# PhaseShifterB.net
KiCad netlist of a schematic drawn in Altium Designer
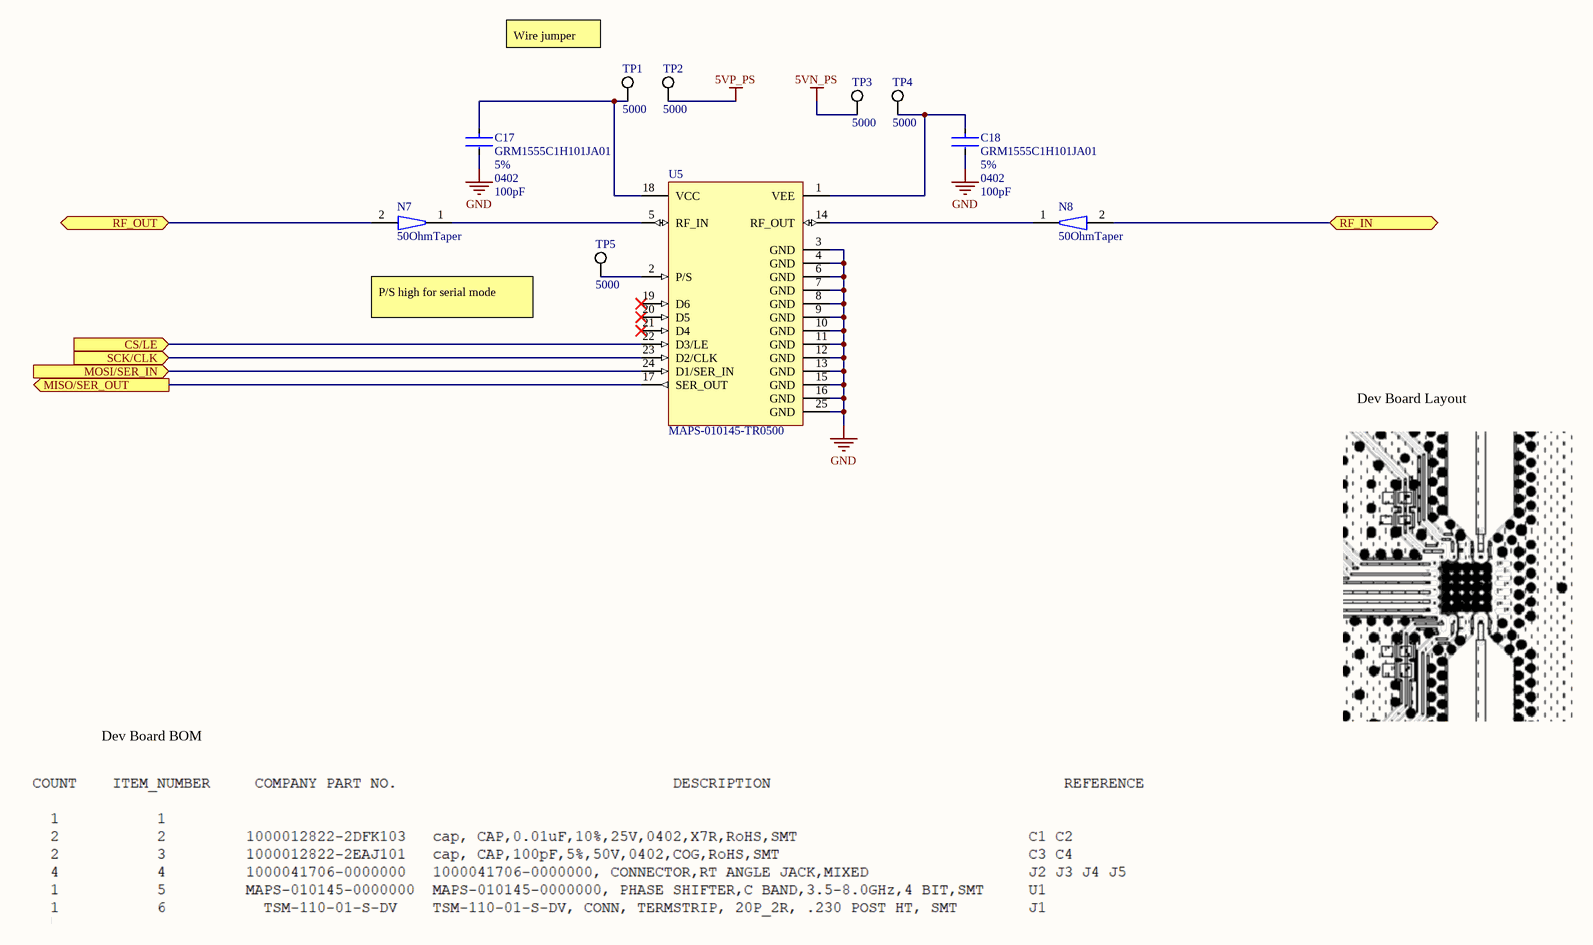
[diagram p0: PhaseShifterB.SchDoc]

(export (version "E")
  (design (tool "Eeschema 10.0.6"))
  (components
    (comp (ref "C17")
      (value "GRM1555C1H101JA01")
      (footprint "Capacitor0402_Murata")
      (description "100 pF ±5% 50V Ceramic Capacitor C0G, NP0 0402 (1005 Metric)")
      (fields
        (field (name "TOLERANCE") "5%")
        (field (name "PACKAGE") "0402")
        (field (name "ALTIUM_VALUE") "100pF")
      )
      (libsource (lib "EECS430PhasedArray") (part "GRM1555C1H101JA01"))
    )
    (comp (ref "C18")
      (value "GRM1555C1H101JA01")
      (footprint "Capacitor0402_Murata")
      (description "100 pF ±5% 50V Ceramic Capacitor C0G, NP0 0402 (1005 Metric)")
      (fields
        (field (name "TOLERANCE") "5%")
        (field (name "PACKAGE") "0402")
        (field (name "ALTIUM_VALUE") "100pF")
      )
      (libsource (lib "EECS430PhasedArray") (part "GRM1555C1H101JA01"))
    )
    (comp (ref "N7")
      (value "50OhmTaper")
      (footprint "50OhmTaper")
      (description "Triangular taper from 50 Ohms to 0402 width")
      (libsource (lib "EECS430PhasedArray") (part "50OhmTaper"))
    )
    (comp (ref "N8")
      (value "50OhmTaper")
      (footprint "50OhmTaper")
      (description "Triangular taper from 50 Ohms to 0402 width")
      (libsource (lib "EECS430PhasedArray") (part "50OhmTaper"))
    )
    (comp (ref "TP1")
      (value "5000")
      (footprint "FP-5000-MFG")
      (description "Red PC Test Point, Miniature Phosphor Bronze Silver Plating Through Hole Mounting Type")
      (libsource (lib "EECS430PhasedArray") (part "5000"))
    )
    (comp (ref "TP2")
      (value "5000")
      (footprint "FP-5000-MFG")
      (description "Red PC Test Point, Miniature Phosphor Bronze Silver Plating Through Hole Mounting Type")
      (libsource (lib "EECS430PhasedArray") (part "5000"))
    )
    (comp (ref "TP3")
      (value "5000")
      (footprint "FP-5000-MFG")
      (description "Red PC Test Point, Miniature Phosphor Bronze Silver Plating Through Hole Mounting Type")
      (libsource (lib "EECS430PhasedArray") (part "5000"))
    )
    (comp (ref "TP4")
      (value "5000")
      (footprint "FP-5000-MFG")
      (description "Red PC Test Point, Miniature Phosphor Bronze Silver Plating Through Hole Mounting Type")
      (libsource (lib "EECS430PhasedArray") (part "5000"))
    )
    (comp (ref "TP5")
      (value "5000")
      (footprint "FP-5000-MFG")
      (description "Red PC Test Point, Miniature Phosphor Bronze Silver Plating Through Hole Mounting Type")
      (libsource (lib "EECS430PhasedArray") (part "5000"))
    )
    (comp (ref "U5")
      (value "MAPS-010145-TR0500")
      (footprint "MAPS-010145-TR0500_QFN50P400X400X100_HS-25N")
      (description "Phase Detectors / Shifters 3.5-6.0GHz 4-Bit Step 22.5 deg.")
      (libsource (lib "EECS430PhasedArray") (part "MAPS-010145-TR0500"))
    )
  )
  (nets
    (net (code "1") (name "/CS{slash}LE") (class "Default")
      (node (ref "U5") (pin "22") (pinfunction "D3/LE_22") (pintype "input"))
    )
    (net (code "2") (name "/MISO{slash}SER_OUT") (class "Default")
      (node (ref "U5") (pin "17") (pinfunction "SER_OUT_17") (pintype "output"))
    )
    (net (code "3") (name "/MOSI{slash}SER_IN") (class "Default")
      (node (ref "U5") (pin "24") (pinfunction "D1/SER_IN_24") (pintype "input"))
    )
    (net (code "4") (name "/RF_IN") (class "Default")
      (node (ref "N8") (pin "2") (pinfunction "2_2") (pintype "passive"))
    )
    (net (code "5") (name "/RF_OUT") (class "Default")
      (node (ref "N7") (pin "2") (pinfunction "2_2") (pintype "passive"))
    )
    (net (code "6") (name "/SCK{slash}CLK") (class "Default")
      (node (ref "U5") (pin "23") (pinfunction "D2/CLK_23") (pintype "input"))
    )
    (net (code "7") (name "5VN_PS") (class "Default")
      (node (ref "TP3") (pin "1") (pinfunction "1_1") (pintype "passive"))
    )
    (net (code "8") (name "5VP_PS") (class "Default")
      (node (ref "TP2") (pin "1") (pinfunction "1_1") (pintype "passive"))
    )
    (net (code "9") (name "GND") (class "Default")
      (node (ref "C17") (pin "2") (pinfunction "2_2") (pintype "passive"))
      (node (ref "C18") (pin "2") (pinfunction "2_2") (pintype "passive"))
      (node (ref "U5") (pin "10") (pinfunction "GND_10") (pintype "power_in"))
      (node (ref "U5") (pin "11") (pinfunction "GND_11") (pintype "power_in"))
      (node (ref "U5") (pin "12") (pinfunction "GND_12") (pintype "power_in"))
      (node (ref "U5") (pin "13") (pinfunction "GND_13") (pintype "power_in"))
      (node (ref "U5") (pin "15") (pinfunction "GND_15") (pintype "power_in"))
      (node (ref "U5") (pin "16") (pinfunction "GND_16") (pintype "power_in"))
      (node (ref "U5") (pin "25") (pinfunction "GND_25") (pintype "power_in"))
      (node (ref "U5") (pin "3") (pinfunction "GND_3") (pintype "power_in"))
      (node (ref "U5") (pin "4") (pinfunction "GND_4") (pintype "power_in"))
      (node (ref "U5") (pin "6") (pinfunction "GND_6") (pintype "power_in"))
      (node (ref "U5") (pin "7") (pinfunction "GND_7") (pintype "power_in"))
      (node (ref "U5") (pin "8") (pinfunction "GND_8") (pintype "power_in"))
      (node (ref "U5") (pin "9") (pinfunction "GND_9") (pintype "power_in"))
    )
    (net (code "10") (name "Net-(U5-P{slash}S)") (class "Default")
      (node (ref "TP5") (pin "1") (pinfunction "1_1") (pintype "passive"))
      (node (ref "U5") (pin "2") (pinfunction "P/S_2") (pintype "input"))
    )
    (net (code "11") (name "Net-(U5-RF_IN)") (class "Default")
      (node (ref "N7") (pin "1") (pinfunction "1_1") (pintype "passive"))
      (node (ref "U5") (pin "5") (pinfunction "RF_IN_5") (pintype "bidirectional"))
    )
    (net (code "12") (name "Net-(U5-RF_OUT)") (class "Default")
      (node (ref "N8") (pin "1") (pinfunction "1_1") (pintype "passive"))
      (node (ref "U5") (pin "14") (pinfunction "RF_OUT_14") (pintype "bidirectional"))
    )
    (net (code "13") (name "Net-(U5-VCC)") (class "Default")
      (node (ref "C17") (pin "1") (pinfunction "1_1") (pintype "passive"))
      (node (ref "TP1") (pin "1") (pinfunction "1_1") (pintype "passive"))
      (node (ref "U5") (pin "18") (pinfunction "VCC_18") (pintype "power_in"))
    )
    (net (code "14") (name "Net-(U5-VEE)") (class "Default")
      (node (ref "C18") (pin "1") (pinfunction "1_1") (pintype "passive"))
      (node (ref "TP4") (pin "1") (pinfunction "1_1") (pintype "passive"))
      (node (ref "U5") (pin "1") (pinfunction "VEE_1") (pintype "power_in"))
    )
    (net (code "15") (name "unconnected-(U5-D4-Pad21)") (class "Default")
      (node (ref "U5") (pin "21") (pinfunction "D4_21") (pintype "input+no_connect"))
    )
    (net (code "16") (name "unconnected-(U5-D5-Pad20)") (class "Default")
      (node (ref "U5") (pin "20") (pinfunction "D5_20") (pintype "input+no_connect"))
    )
    (net (code "17") (name "unconnected-(U5-D6-Pad19)") (class "Default")
      (node (ref "U5") (pin "19") (pinfunction "D6_19") (pintype "input+no_connect"))
    )
  )
)
